# Sheet2.net
KiCad netlist of a schematic drawn in Altium Designer
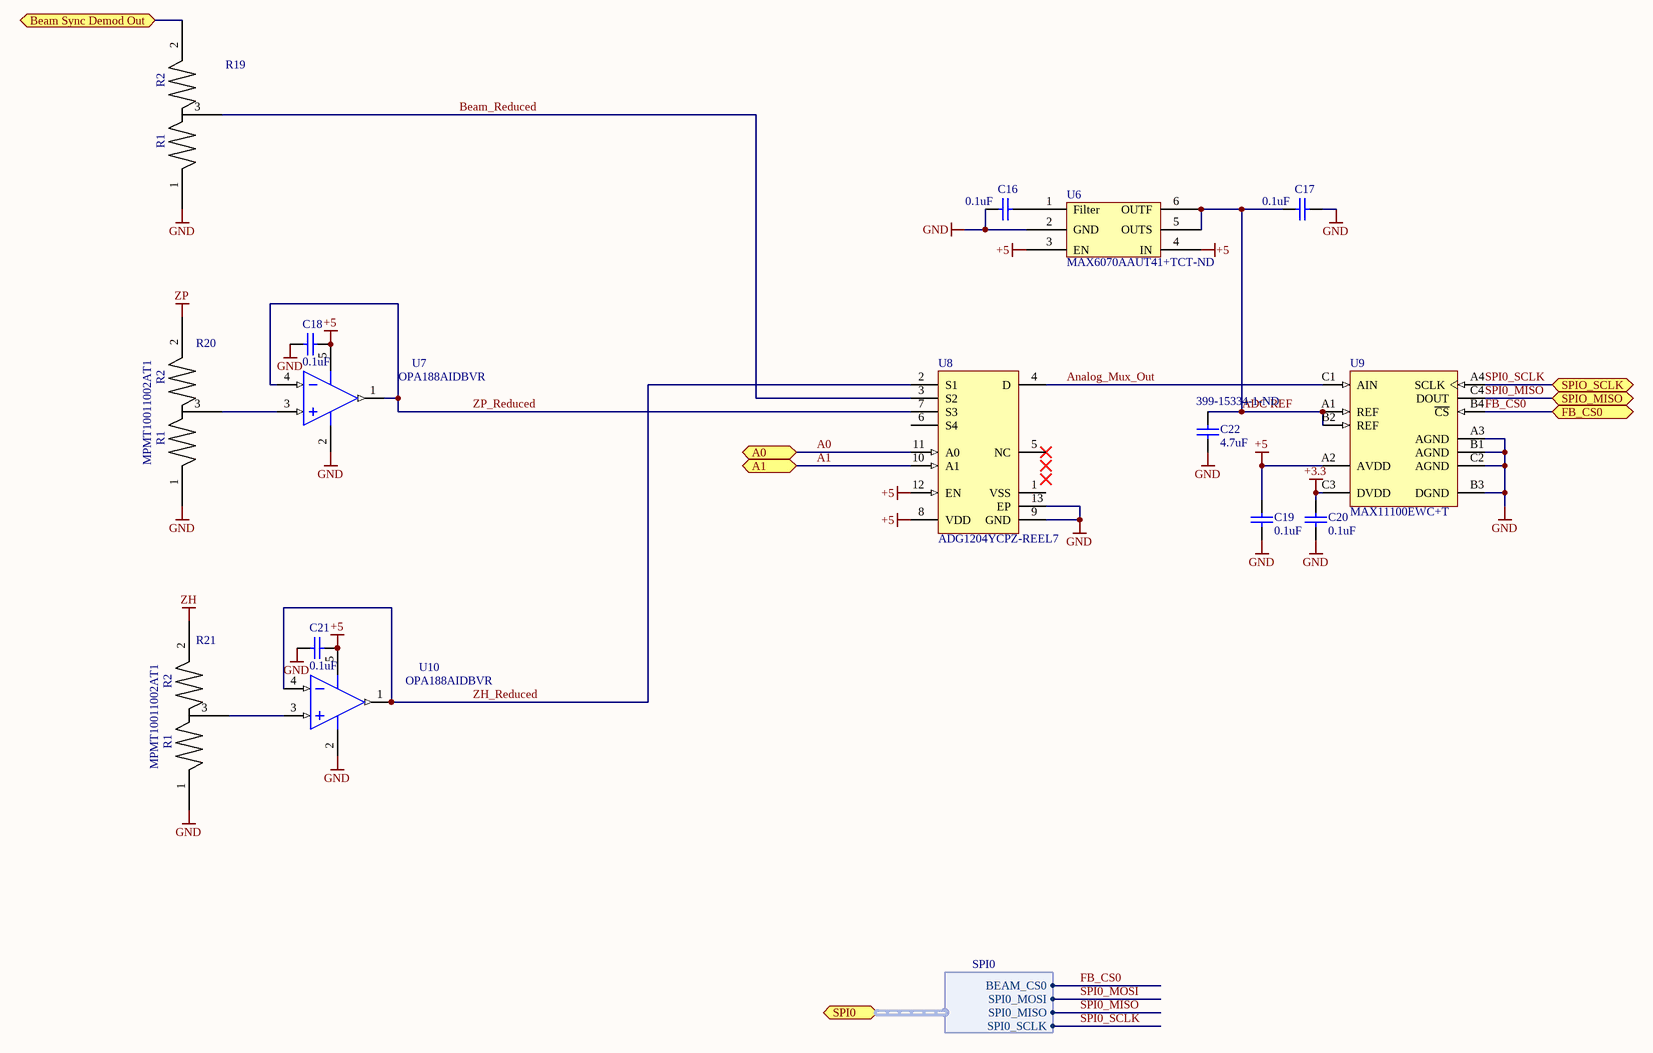
[diagram p0: Sheet2.SchDoc]

(export (version "E")
  (design (tool "Eeschema 10.0.6"))
  (components
    (comp (ref "C16")
      (value "0.1uF")
      (footprint "CAPC0402(1005)60_L")
      (description "CAP CER 0.1UF 10V X7R 0402")
      (fields
        (field (name "MANUFACTURER") "Murata Electronics North America")
        (field (name "MANUFACTURER PART NUMBER") "GRM155R71A104KA01D")
      )
      (libsource (lib "Altium Content Vault") (part "CMP-1034-00252-1"))
    )
    (comp (ref "C17")
      (value "0.1uF")
      (footprint "CAPC0402(1005)60_L")
      (description "CAP CER 0.1UF 10V X7R 0402")
      (fields
        (field (name "MANUFACTURER") "Murata Electronics North America")
        (field (name "MANUFACTURER PART NUMBER") "GRM155R71A104KA01D")
      )
      (libsource (lib "Altium Content Vault") (part "CMP-1034-00252-1"))
    )
    (comp (ref "C18")
      (value "0.1uF")
      (footprint "CAPC0402(1005)60_L")
      (description "CAP CER 0.1UF 10V X7R 0402")
      (fields
        (field (name "MANUFACTURER") "Murata Electronics North America")
        (field (name "MANUFACTURER PART NUMBER") "GRM155R71A104KA01D")
      )
      (libsource (lib "Altium Content Vault") (part "CMP-1034-00252-1"))
    )
    (comp (ref "C19")
      (value "0.1uF")
      (footprint "CAPC0402(1005)60_L")
      (description "CAP CER 0.1UF 10V X7R 0402")
      (fields
        (field (name "MANUFACTURER") "Murata Electronics North America")
        (field (name "MANUFACTURER PART NUMBER") "GRM155R71A104KA01D")
      )
      (libsource (lib "Altium Content Vault") (part "CMP-1034-00252-1"))
    )
    (comp (ref "C20")
      (value "0.1uF")
      (footprint "CAPC0402(1005)60_L")
      (description "CAP CER 0.1UF 10V X7R 0402")
      (fields
        (field (name "MANUFACTURER") "Murata Electronics North America")
        (field (name "MANUFACTURER PART NUMBER") "GRM155R71A104KA01D")
      )
      (libsource (lib "Altium Content Vault") (part "CMP-1034-00252-1"))
    )
    (comp (ref "C21")
      (value "0.1uF")
      (footprint "CAPC0402(1005)60_L")
      (description "CAP CER 0.1UF 10V X7R 0402")
      (fields
        (field (name "MANUFACTURER") "Murata Electronics North America")
        (field (name "MANUFACTURER PART NUMBER") "GRM155R71A104KA01D")
      )
      (libsource (lib "Altium Content Vault") (part "CMP-1034-00252-1"))
    )
    (comp (ref "C22")
      (value "4.7uF")
      (footprint "CAPC0402(1005)60_L")
      (description "CAP CER 4.7UF 10V X7R 0402")
      (fields
        (field (name "SUPPLIER PART NUMBER 1") "399-15334-1-ND")
        (field (name "MANUFACTURER") "KEMET")
        (field (name "MANUFACTURER PART NUMBER") "C0402C479D4GAC7867")
      )
      (libsource (lib "Altium Content Vault") (part "CMP-1034-00252-1"))
    )
    (comp (ref "R19")
      (value "MPM")
      (footprint "SOT95P230X102-3N-MPM")
      (libsource (lib "ZLS_Schematic_lib") (part "MPM"))
    )
    (comp (ref "R20")
      (value "MPMT10011002AT1")
      (footprint "SOT95P230X102-3N-MPM")
      (description "RES NTWRK 2 RES MULT OHM TO236-3")
      (fields (field (name "MANUFACTURER") "Vishay Thin Film") (field (name "TOLERANCE") "±0.1%"))
      (libsource (lib "ZLS_Schematic_lib") (part "MPM"))
    )
    (comp (ref "R21")
      (value "MPMT10011002AT1")
      (footprint "SOT95P230X102-3N-MPM")
      (description "RES NTWRK 2 RES MULT OHM TO236-3")
      (fields (field (name "MANUFACTURER") "Vishay Thin Film") (field (name "TOLERANCE") "±0.1%"))
      (libsource (lib "ZLS_Schematic_lib") (part "MPM"))
    )
    (comp (ref "U6")
      (value "MAX6070AAUT41+T")
      (footprint "SOT95P280X445-6N")
      (description "IC VREF SERIES 4.096V SOT23")
      (fields
        (field (name "SUPPLIER PART NUMBER 1") "MAX6070AAUT41+TCT-ND")
        (field (name "MANUFACTURER") "Maxim Integrated")
        (field (name "TOLERANCE") "±0.04%")
      )
      (libsource (lib "ZLS_Schematic_lib") (part "MAX6070AAUT41+T"))
    )
    (comp (ref "U7")
      (value "OPA188AIDBVR")
      (footprint "DBV0005A_M")
      (fields (field (name "MANUFACTURER") "Texas Instruments"))
      (libsource (lib "Altium Content Vault") (part "CMP-0809-00005-2"))
    )
    (comp (ref "U8")
      (value "ADG1204YCPZ-REEL7")
      (footprint "ADI-CP-12-1_L")
      (fields (field (name "MANUFACTURER") "Analog Devices"))
      (libsource (lib "Altium Content Vault") (part "CMP-0793-00001-1"))
    )
    (comp (ref "U9")
      (value "MAX11100EWC+T")
      (footprint "W121A2+1")
      (description "16-Bit, +5V, 200ksps ADC with 10uA Shutdown, 12-Pin WLP, -40°C to +85°C, Pb-Free, Tape and Reel")
      (libsource (lib "Altium Content Vault") (part "CON-ADC-MAX11100-SQ12"))
    )
    (comp (ref "U10")
      (value "OPA188AIDBVR")
      (footprint "DBV0005A_M")
      (fields (field (name "MANUFACTURER") "Texas Instruments"))
      (libsource (lib "Altium Content Vault") (part "CMP-0809-00005-2"))
    )
  )
  (nets
    (net (code "2") (name "+3.3") (class "Default")
      (node (ref "C20") (pin "1") (pinfunction "1_1") (pintype "passive"))
      (node (ref "U9") (pin "C3") (pinfunction "DVDD_C3") (pintype "power_in"))
    )
    (net (code "3") (name "+5") (class "Default")
      (node (ref "C18") (pin "2") (pinfunction "2_2") (pintype "passive"))
      (node (ref "C19") (pin "1") (pinfunction "1_1") (pintype "passive"))
      (node (ref "C21") (pin "2") (pinfunction "2_2") (pintype "passive"))
      (node (ref "U10") (pin "5") (pinfunction "V+_5") (pintype "power_in"))
      (node (ref "U6") (pin "3") (pinfunction "EN_3") (pintype "passive"))
      (node (ref "U6") (pin "4") (pinfunction "IN_4") (pintype "passive"))
      (node (ref "U7") (pin "5") (pinfunction "V+_5") (pintype "power_in"))
      (node (ref "U8") (pin "12") (pinfunction "EN_12") (pintype "input"))
      (node (ref "U8") (pin "8") (pinfunction "VDD_8") (pintype "power_in"))
      (node (ref "U9") (pin "A2") (pinfunction "AVDD_A2") (pintype "power_in"))
    )
    (net (code "4") (name "/A0") (class "Default")
      (node (ref "U8") (pin "11") (pinfunction "A0_11") (pintype "input"))
    )
    (net (code "5") (name "/A1") (class "Default")
      (node (ref "U8") (pin "10") (pinfunction "A1_10") (pintype "input"))
    )
    (net (code "6") (name "/ADC REF") (class "Default")
      (node (ref "C17") (pin "2") (pinfunction "2_2") (pintype "passive"))
      (node (ref "C22") (pin "1") (pinfunction "1_1") (pintype "passive"))
      (node (ref "U6") (pin "5") (pinfunction "OUTS_5") (pintype "passive"))
      (node (ref "U6") (pin "6") (pinfunction "OUTF_6") (pintype "passive"))
      (node (ref "U9") (pin "A1") (pinfunction "REF_A1") (pintype "input"))
      (node (ref "U9") (pin "B2") (pinfunction "REF_B2") (pintype "input"))
    )
    (net (code "7") (name "/Analog_Mux_Out") (class "Default")
      (node (ref "U8") (pin "4") (pinfunction "D_4") (pintype "passive"))
      (node (ref "U9") (pin "C1") (pinfunction "AIN_C1") (pintype "input"))
    )
    (net (code "8") (name "/Beam Sync Demod Out") (class "Default")
      (node (ref "R19") (pin "2") (pinfunction "2_2") (pintype "passive"))
    )
    (net (code "9") (name "/Beam_Reduced") (class "Default")
      (node (ref "R19") (pin "3") (pinfunction "3_3") (pintype "passive"))
      (node (ref "U8") (pin "3") (pinfunction "S2_3") (pintype "passive"))
    )
    (net (code "10") (name "/FB_CS0") (class "Default")
      (node (ref "U9") (pin "B4") (pinfunction "~{CS}_B4") (pintype "input"))
    )
    (net (code "11") (name "/SPI0_MISO") (class "Default")
      (node (ref "U9") (pin "C4") (pinfunction "DOUT_C4") (pintype "tri_state"))
    )
    (net (code "13") (name "/SPI0_SCLK") (class "Default")
      (node (ref "U9") (pin "A4") (pinfunction "SCLK_A4") (pintype "input"))
    )
    (net (code "14") (name "/ZH_Reduced") (class "Default")
      (node (ref "U10") (pin "1") (pinfunction "OUT_1") (pintype "output"))
      (node (ref "U10") (pin "4") (pinfunction "IN-_4") (pintype "input"))
      (node (ref "U8") (pin "2") (pinfunction "S1_2") (pintype "passive"))
    )
    (net (code "15") (name "/ZP_Reduced") (class "Default")
      (node (ref "U7") (pin "1") (pinfunction "OUT_1") (pintype "output"))
      (node (ref "U7") (pin "4") (pinfunction "IN-_4") (pintype "input"))
      (node (ref "U8") (pin "7") (pinfunction "S3_7") (pintype "passive"))
    )
    (net (code "17") (name "GND") (class "Default")
      (node (ref "C16") (pin "2") (pinfunction "2_2") (pintype "passive"))
      (node (ref "C17") (pin "1") (pinfunction "1_1") (pintype "passive"))
      (node (ref "C18") (pin "1") (pinfunction "1_1") (pintype "passive"))
      (node (ref "C19") (pin "2") (pinfunction "2_2") (pintype "passive"))
      (node (ref "C20") (pin "2") (pinfunction "2_2") (pintype "passive"))
      (node (ref "C21") (pin "1") (pinfunction "1_1") (pintype "passive"))
      (node (ref "C22") (pin "2") (pinfunction "2_2") (pintype "passive"))
      (node (ref "R19") (pin "1") (pinfunction "1_1") (pintype "passive"))
      (node (ref "R20") (pin "1") (pinfunction "1_1") (pintype "passive"))
      (node (ref "R21") (pin "1") (pinfunction "1_1") (pintype "passive"))
      (node (ref "U10") (pin "2") (pinfunction "V-_2") (pintype "power_in"))
      (node (ref "U6") (pin "2") (pinfunction "GND_2") (pintype "passive"))
      (node (ref "U7") (pin "2") (pinfunction "V-_2") (pintype "power_in"))
      (node (ref "U8") (pin "13") (pinfunction "EP_13") (pintype "power_in"))
      (node (ref "U8") (pin "9") (pinfunction "GND_9") (pintype "power_in"))
      (node (ref "U9") (pin "A3") (pinfunction "AGND_A3") (pintype "power_in"))
      (node (ref "U9") (pin "B1") (pinfunction "AGND_B1") (pintype "power_in"))
      (node (ref "U9") (pin "B3") (pinfunction "DGND_B3") (pintype "power_in"))
      (node (ref "U9") (pin "C2") (pinfunction "AGND_C2") (pintype "power_in"))
    )
    (net (code "18") (name "Net-(U6-Filter)") (class "Default")
      (node (ref "C16") (pin "1") (pinfunction "1_1") (pintype "passive"))
      (node (ref "U6") (pin "1") (pinfunction "Filter_1") (pintype "passive"))
    )
    (net (code "19") (name "Net-(U7-IN+)") (class "Default")
      (node (ref "R20") (pin "3") (pinfunction "3_3") (pintype "passive"))
      (node (ref "U7") (pin "3") (pinfunction "IN+_3") (pintype "input"))
    )
    (net (code "20") (name "Net-(U10-IN+)") (class "Default")
      (node (ref "R21") (pin "3") (pinfunction "3_3") (pintype "passive"))
      (node (ref "U10") (pin "3") (pinfunction "IN+_3") (pintype "input"))
    )
    (net (code "21") (name "ZH") (class "Default")
      (node (ref "R21") (pin "2") (pinfunction "2_2") (pintype "passive"))
    )
    (net (code "22") (name "ZP") (class "Default")
      (node (ref "R20") (pin "2") (pinfunction "2_2") (pintype "passive"))
    )
    (net (code "23") (name "unconnected-(U8-NC-Pad5)") (class "Default")
      (node (ref "U8") (pin "5") (pinfunction "NC_5") (pintype "passive+no_connect"))
    )
    (net (code "24") (name "unconnected-(U8-S4-Pad6)") (class "Default")
      (node (ref "U8") (pin "6") (pinfunction "S4_6") (pintype "passive"))
    )
    (net (code "25") (name "unconnected-(U8-VSS-Pad1)") (class "Default")
      (node (ref "U8") (pin "1") (pinfunction "VSS_1") (pintype "power_in"))
    )
  )
)
